# Sheet1.net
KiCad netlist of a schematic drawn in Altium Designer
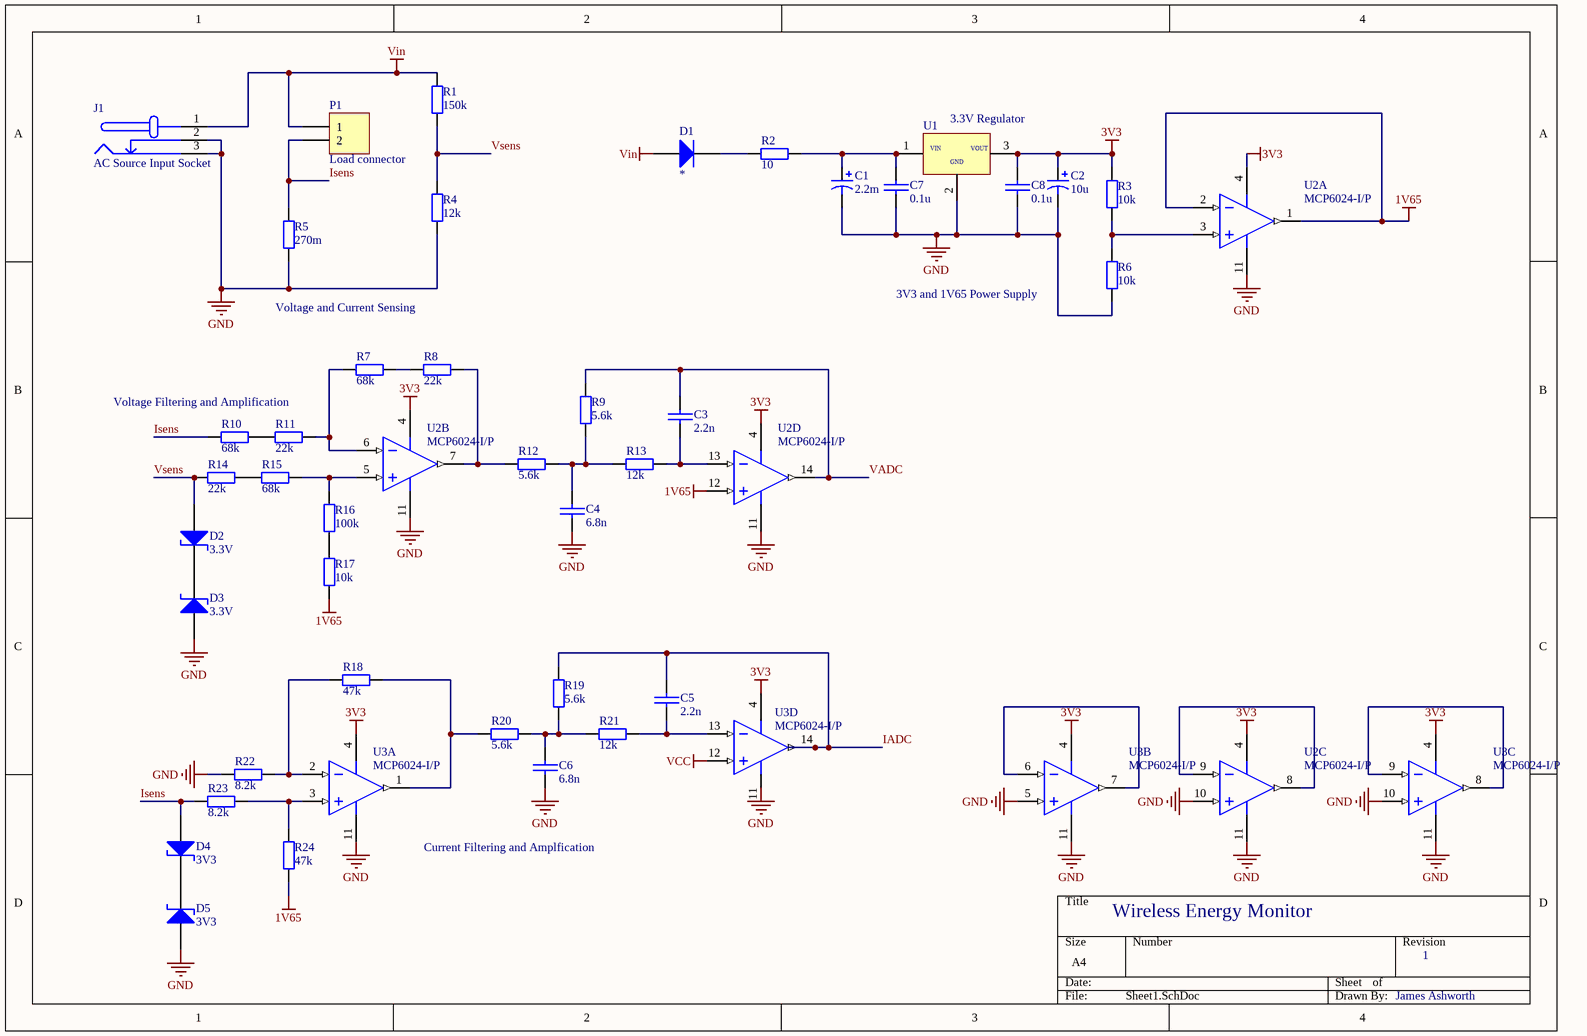
[diagram p0: Sheet1.SchDoc]

(export (version "E")
  (design (tool "Eeschema 10.0.6"))
  (components
    (comp (ref "C1")
      (value "2.2m")
      (footprint "CAP-RAD-7.5mm Pitch")
      (description "Polarized Capacitor (Axial)")
      (fields (field (name "PUBLISHER") "Altium Limited"))
      (libsource (lib "EE209_SCHLibrary") (part "Cap Pol (220uF-470uF)"))
    )
    (comp (ref "C2")
      (value "10u")
      (footprint "CAP-RAD-3mm Pitch")
      (description "Polarized Capacitor (Axial)")
      (fields (field (name "PUBLISHER") "Altium Limited"))
      (libsource (lib "EE209_SCHLibrary") (part "Cap Pol (22uF-100uF)"))
    )
    (comp (ref "C3")
      (value "2.2n")
      (footprint "ECE-CAPR0.2x0.1TH")
      (description "CAP CER 10pF 50V TH")
      (libsource (lib "EceParts") (part "Cap"))
    )
    (comp (ref "C4")
      (value "6.8n")
      (footprint "ECE-CAPR0.2x0.1TH")
      (description "CAP CER 10pF 50V TH")
      (libsource (lib "EceParts") (part "Cap"))
    )
    (comp (ref "C5")
      (value "2.2n")
      (footprint "ECE-CAPR0.2x0.1TH")
      (description "CAP CER 10pF 50V TH")
      (libsource (lib "EceParts") (part "Cap"))
    )
    (comp (ref "C6")
      (value "6.8n")
      (footprint "ECE-CAPR0.2x0.1TH")
      (description "CAP CER 10pF 50V TH")
      (libsource (lib "EceParts") (part "Cap"))
    )
    (comp (ref "C7")
      (value "0.1u")
      (footprint "ECE-CAPR0.2x0.1TH")
      (description "CAP CER 10pF 50V TH")
      (libsource (lib "EceParts") (part "Cap"))
    )
    (comp (ref "C8")
      (value "0.1u")
      (footprint "ECE-CAPR0.2x0.1TH")
      (description "CAP CER 10pF 50V TH")
      (libsource (lib "EceParts") (part "Cap"))
    )
    (comp (ref "D1")
      (value "*")
      (footprint "AXIAL-DIODE-0.4")
      (fields
        (field (name "MANUFACTURER") "Fairchild Semiconductor")
        (field (name "PUBLISHER") "Altium Limited")
      )
      (libsource (lib "EE209_SCHLibrary") (part "Diode"))
    )
    (comp (ref "D2")
      (value "3.3V")
      (footprint "AXIAL-DIODE-0.4")
      (description "Zener Diode")
      (libsource (lib "EE209_SCHLibrary") (part "Zener"))
    )
    (comp (ref "D3")
      (value "3.3V")
      (footprint "AXIAL-DIODE-0.4")
      (description "Zener Diode")
      (libsource (lib "EE209_SCHLibrary") (part "Zener"))
    )
    (comp (ref "D4")
      (value "3V3")
      (footprint "AXIAL-DIODE-0.4")
      (description "Zener Diode")
      (libsource (lib "EE209_SCHLibrary") (part "Zener"))
    )
    (comp (ref "D5")
      (value "3V3")
      (footprint "AXIAL-DIODE-0.4")
      (description "Zener Diode")
      (libsource (lib "EE209_SCHLibrary") (part "Zener"))
    )
    (comp (ref "J1")
      (value "AC Source Input Socket")
      (footprint "AC-Socket")
      (libsource (lib "EE209_SCHLibrary") (part "AC Input"))
    )
    (comp (ref "P1")
      (value "Load connector")
      (footprint "Dual Banana Plug")
      (description "M6 Holes")
      (fields (field (name "PUBLISHER") "Altium Limited"))
      (libsource (lib "EE209_SCHLibrary") (part "Dual Banana Plugs"))
    )
    (comp (ref "R1")
      (value "150k")
      (footprint "AXIAL-0.4")
      (description "Through Hole Resistor")
      (fields (field (name "PUBLISHER") "Altium Limited"))
      (libsource (lib "") (part "Res_1"))
    )
    (comp (ref "R2")
      (value "10")
      (footprint "AXIAL-0.4")
      (description "Through Hole Resistor")
      (fields (field (name "PUBLISHER") "Altium Limited"))
      (libsource (lib "EE209_SCHLibrary") (part "Res"))
    )
    (comp (ref "R3")
      (value "10k")
      (footprint "AXIAL-0.4")
      (description "Through Hole Resistor")
      (fields (field (name "PUBLISHER") "Altium Limited"))
      (libsource (lib "") (part "Res_1"))
    )
    (comp (ref "R4")
      (value "12k")
      (footprint "AXIAL-0.4")
      (description "Through Hole Resistor")
      (fields (field (name "PUBLISHER") "Altium Limited"))
      (libsource (lib "") (part "Res_1"))
    )
    (comp (ref "R5")
      (value "270m")
      (footprint "0805 RES")
      (description "Through Hole Resistor")
      (fields (field (name "PUBLISHER") "Altium Limited"))
      (libsource (lib "") (part "Res_1"))
    )
    (comp (ref "R6")
      (value "10k")
      (footprint "AXIAL-0.4")
      (description "Through Hole Resistor")
      (fields (field (name "PUBLISHER") "Altium Limited"))
      (libsource (lib "") (part "Res_1"))
    )
    (comp (ref "R7")
      (value "68k")
      (footprint "AXIAL-0.4")
      (description "Through Hole Resistor")
      (fields (field (name "PUBLISHER") "Altium Limited"))
      (libsource (lib "EE209_SCHLibrary") (part "Res"))
    )
    (comp (ref "R8")
      (value "22k")
      (footprint "AXIAL-0.4")
      (description "Through Hole Resistor")
      (fields (field (name "PUBLISHER") "Altium Limited"))
      (libsource (lib "EE209_SCHLibrary") (part "Res"))
    )
    (comp (ref "R9")
      (value "5.6k")
      (footprint "0805 RES")
      (description "Through Hole Resistor")
      (fields (field (name "PUBLISHER") "Altium Limited"))
      (libsource (lib "") (part "Res_1"))
    )
    (comp (ref "R10")
      (value "68k")
      (footprint "AXIAL-0.4")
      (description "Through Hole Resistor")
      (fields (field (name "PUBLISHER") "Altium Limited"))
      (libsource (lib "EE209_SCHLibrary") (part "Res"))
    )
    (comp (ref "R11")
      (value "22k")
      (footprint "AXIAL-0.4")
      (description "Through Hole Resistor")
      (fields (field (name "PUBLISHER") "Altium Limited"))
      (libsource (lib "EE209_SCHLibrary") (part "Res"))
    )
    (comp (ref "R12")
      (value "5.6k")
      (footprint "AXIAL-0.4")
      (description "Through Hole Resistor")
      (fields (field (name "PUBLISHER") "Altium Limited"))
      (libsource (lib "EE209_SCHLibrary") (part "Res"))
    )
    (comp (ref "R13")
      (value "12k")
      (footprint "0805 RES")
      (description "Through Hole Resistor")
      (fields (field (name "PUBLISHER") "Altium Limited"))
      (libsource (lib "") (part "Res_2"))
    )
    (comp (ref "R14")
      (value "22k")
      (footprint "AXIAL-0.4")
      (description "Through Hole Resistor")
      (fields (field (name "PUBLISHER") "Altium Limited"))
      (libsource (lib "EE209_SCHLibrary") (part "Res"))
    )
    (comp (ref "R15")
      (value "68k")
      (footprint "AXIAL-0.4")
      (description "Through Hole Resistor")
      (fields (field (name "PUBLISHER") "Altium Limited"))
      (libsource (lib "EE209_SCHLibrary") (part "Res"))
    )
    (comp (ref "R16")
      (value "100k")
      (footprint "AXIAL-0.4")
      (description "Through Hole Resistor")
      (fields (field (name "PUBLISHER") "Altium Limited"))
      (libsource (lib "") (part "Res_1"))
    )
    (comp (ref "R17")
      (value "10k")
      (footprint "AXIAL-0.4")
      (description "Through Hole Resistor")
      (fields (field (name "PUBLISHER") "Altium Limited"))
      (libsource (lib "") (part "Res_1"))
    )
    (comp (ref "R18")
      (value "47k")
      (footprint "AXIAL-0.4")
      (description "Through Hole Resistor")
      (fields (field (name "PUBLISHER") "Altium Limited"))
      (libsource (lib "") (part "Res_2"))
    )
    (comp (ref "R19")
      (value "5.6k")
      (footprint "AXIAL-0.4")
      (description "Through Hole Resistor")
      (fields (field (name "PUBLISHER") "Altium Limited"))
      (libsource (lib "") (part "Res_3"))
    )
    (comp (ref "R20")
      (value "5.6k")
      (footprint "AXIAL-0.4")
      (description "Through Hole Resistor")
      (fields (field (name "PUBLISHER") "Altium Limited"))
      (libsource (lib "") (part "Res_2"))
    )
    (comp (ref "R21")
      (value "12k")
      (footprint "AXIAL-0.4")
      (description "Through Hole Resistor")
      (fields (field (name "PUBLISHER") "Altium Limited"))
      (libsource (lib "") (part "Res_2"))
    )
    (comp (ref "R22")
      (value "8.2k")
      (footprint "AXIAL-0.4")
      (description "Through Hole Resistor")
      (fields (field (name "PUBLISHER") "Altium Limited"))
      (libsource (lib "EE209_SCHLibrary") (part "Res"))
    )
    (comp (ref "R23")
      (value "8.2k")
      (footprint "AXIAL-0.4")
      (description "Through Hole Resistor")
      (fields (field (name "PUBLISHER") "Altium Limited"))
      (libsource (lib "EE209_SCHLibrary") (part "Res"))
    )
    (comp (ref "R24")
      (value "47k")
      (footprint "AXIAL-0.4")
      (description "Through Hole Resistor")
      (fields (field (name "PUBLISHER") "Altium Limited"))
      (libsource (lib "") (part "Res_1"))
    )
    (comp (ref "U1")
      (value "3.3V Regulator")
      (footprint "TO-92")
      (libsource (lib "EE209_SCHLibrary") (part "LP2950-33"))
    )
    (comp (ref "U2")
      (value "MCP6024-I/P")
      (footprint "DIP-14")
      (description "Rail-to-Rail Input/Output, 10 MHz Operational Amplifier, 14-Pin PDIP, Industrial Temperature")
      (fields (field (name "PUBLISHER") "Altium Limited"))
      (libsource (lib "EE209_SCHLibrary") (part "MCP6024-I/P"))
    )
    (comp (ref "U3")
      (value "MCP6024-I/P")
      (footprint "DIP-14")
      (description "Rail-to-Rail Input/Output, 10 MHz Operational Amplifier, 14-Pin PDIP, Industrial Temperature")
      (fields (field (name "PUBLISHER") "Altium Limited"))
      (libsource (lib "EE209_SCHLibrary") (part "MCP6024-I/P"))
    )
  )
  (nets
    (net (code "1") (name "/IADC") (class "Default")
      (node (ref "C5") (pin "1") (pinfunction "1_1") (pintype "passive"))
      (node (ref "R19") (pin "1") (pinfunction "1_1") (pintype "passive"))
      (node (ref "U3") (pin "14") (pinfunction "VOUTD_14") (pintype "output"))
    )
    (net (code "2") (name "/Isens") (class "Default")
      (node (ref "D4") (pin "1") (pinfunction "A_1") (pintype "passive"))
      (node (ref "P1") (pin "2") (pinfunction "2_2") (pintype "passive"))
      (node (ref "R10") (pin "1") (pinfunction "1_1") (pintype "passive"))
      (node (ref "R23") (pin "1") (pinfunction "1_1") (pintype "passive"))
      (node (ref "R5") (pin "2") (pinfunction "2_2") (pintype "passive"))
    )
    (net (code "3") (name "/VADC") (class "Default")
      (node (ref "C3") (pin "1") (pinfunction "1_1") (pintype "passive"))
      (node (ref "R9") (pin "2") (pinfunction "2_2") (pintype "passive"))
      (node (ref "U2") (pin "14") (pinfunction "VOUTD_14") (pintype "output"))
    )
    (net (code "4") (name "/Vsens") (class "Default")
      (node (ref "D2") (pin "1") (pinfunction "A_1") (pintype "passive"))
      (node (ref "R1") (pin "1") (pinfunction "1_1") (pintype "passive"))
      (node (ref "R14") (pin "1") (pinfunction "1_1") (pintype "passive"))
      (node (ref "R4") (pin "2") (pinfunction "2_2") (pintype "passive"))
    )
    (net (code "5") (name "1V65") (class "Default")
      (node (ref "R17") (pin "1") (pinfunction "1_1") (pintype "passive"))
      (node (ref "R24") (pin "1") (pinfunction "1_1") (pintype "passive"))
      (node (ref "U2") (pin "1") (pinfunction "VOUTA_1") (pintype "output"))
      (node (ref "U2") (pin "12") (pinfunction "VIND+_12") (pintype "input"))
      (node (ref "U2") (pin "2") (pinfunction "VINA-_2") (pintype "input"))
    )
    (net (code "6") (name "3V3") (class "Default")
      (node (ref "C2") (pin "1") (pinfunction "1_1") (pintype "passive"))
      (node (ref "C8") (pin "1") (pinfunction "1_1") (pintype "passive"))
      (node (ref "R3") (pin "2") (pinfunction "2_2") (pintype "passive"))
      (node (ref "U1") (pin "3") (pinfunction "OUTPUT_3") (pintype "passive"))
      (node (ref "U2") (pin "4") (pinfunction "VDD_4") (pintype "power_in"))
      (node (ref "U3") (pin "4") (pinfunction "VDD_4") (pintype "power_in"))
    )
    (net (code "7") (name "GND") (class "Default")
      (node (ref "C1") (pin "2") (pinfunction "2_2") (pintype "passive"))
      (node (ref "C2") (pin "2") (pinfunction "2_2") (pintype "passive"))
      (node (ref "C4") (pin "2") (pinfunction "2_2") (pintype "passive"))
      (node (ref "C6") (pin "2") (pinfunction "2_2") (pintype "passive"))
      (node (ref "C7") (pin "2") (pinfunction "2_2") (pintype "passive"))
      (node (ref "C8") (pin "2") (pinfunction "2_2") (pintype "passive"))
      (node (ref "D3") (pin "1") (pinfunction "A_1") (pintype "passive"))
      (node (ref "D5") (pin "1") (pinfunction "A_1") (pintype "passive"))
      (node (ref "J1") (pin "2") (pinfunction "GND_ALT_2") (pintype "power_in"))
      (node (ref "J1") (pin "3") (pinfunction "GND_3") (pintype "power_in"))
      (node (ref "R22") (pin "1") (pinfunction "1_1") (pintype "passive"))
      (node (ref "R4") (pin "1") (pinfunction "1_1") (pintype "passive"))
      (node (ref "R5") (pin "1") (pinfunction "1_1") (pintype "passive"))
      (node (ref "R6") (pin "1") (pinfunction "1_1") (pintype "passive"))
      (node (ref "U1") (pin "2") (pinfunction "GND_2") (pintype "passive"))
      (node (ref "U2") (pin "10") (pinfunction "VINC+_10") (pintype "input"))
      (node (ref "U2") (pin "11") (pinfunction "VSS_11") (pintype "power_in"))
      (node (ref "U3") (pin "10") (pinfunction "VINC+_10") (pintype "input"))
      (node (ref "U3") (pin "11") (pinfunction "VSS_11") (pintype "power_in"))
      (node (ref "U3") (pin "5") (pinfunction "VINB+_5") (pintype "input"))
    )
    (net (code "8") (name "Net-(C4-Pad1)") (class "Default")
      (node (ref "C4") (pin "1") (pinfunction "1_1") (pintype "passive"))
      (node (ref "R12") (pin "2") (pinfunction "2_2") (pintype "passive"))
      (node (ref "R13") (pin "2") (pinfunction "2_2") (pintype "passive"))
      (node (ref "R9") (pin "1") (pinfunction "1_1") (pintype "passive"))
    )
    (net (code "9") (name "Net-(C6-Pad1)") (class "Default")
      (node (ref "C6") (pin "1") (pinfunction "1_1") (pintype "passive"))
      (node (ref "R19") (pin "2") (pinfunction "2_2") (pintype "passive"))
      (node (ref "R20") (pin "1") (pinfunction "1_1") (pintype "passive"))
      (node (ref "R21") (pin "2") (pinfunction "2_2") (pintype "passive"))
    )
    (net (code "10") (name "Net-(D1-K)") (class "Default")
      (node (ref "D1") (pin "2") (pinfunction "K_2") (pintype "passive"))
      (node (ref "R2") (pin "1") (pinfunction "1_1") (pintype "passive"))
    )
    (net (code "11") (name "Net-(D2-K)") (class "Default")
      (node (ref "D2") (pin "2") (pinfunction "K_2") (pintype "passive"))
      (node (ref "D3") (pin "2") (pinfunction "K_2") (pintype "passive"))
    )
    (net (code "12") (name "Net-(D4-K)") (class "Default")
      (node (ref "D4") (pin "2") (pinfunction "K_2") (pintype "passive"))
      (node (ref "D5") (pin "2") (pinfunction "K_2") (pintype "passive"))
    )
    (net (code "13") (name "Net-(R7-Pad2)") (class "Default")
      (node (ref "R7") (pin "2") (pinfunction "2_2") (pintype "passive"))
      (node (ref "R8") (pin "1") (pinfunction "1_1") (pintype "passive"))
    )
    (net (code "14") (name "Net-(R10-Pad2)") (class "Default")
      (node (ref "R10") (pin "2") (pinfunction "2_2") (pintype "passive"))
      (node (ref "R11") (pin "1") (pinfunction "1_1") (pintype "passive"))
    )
    (net (code "15") (name "Net-(R14-Pad2)") (class "Default")
      (node (ref "R14") (pin "2") (pinfunction "2_2") (pintype "passive"))
      (node (ref "R15") (pin "1") (pinfunction "1_1") (pintype "passive"))
    )
    (net (code "16") (name "Net-(R16-Pad1)") (class "Default")
      (node (ref "R16") (pin "1") (pinfunction "1_1") (pintype "passive"))
      (node (ref "R17") (pin "2") (pinfunction "2_2") (pintype "passive"))
    )
    (net (code "17") (name "Net-(U1-INPUT)") (class "Default")
      (node (ref "C1") (pin "1") (pinfunction "1_1") (pintype "passive"))
      (node (ref "C7") (pin "1") (pinfunction "1_1") (pintype "passive"))
      (node (ref "R2") (pin "2") (pinfunction "2_2") (pintype "passive"))
      (node (ref "U1") (pin "1") (pinfunction "INPUT_1") (pintype "passive"))
    )
    (net (code "18") (name "Net-(U2A-VINA+)") (class "Default")
      (node (ref "R3") (pin "1") (pinfunction "1_1") (pintype "passive"))
      (node (ref "R6") (pin "2") (pinfunction "2_2") (pintype "passive"))
      (node (ref "U2") (pin "3") (pinfunction "VINA+_3") (pintype "input"))
    )
    (net (code "19") (name "Net-(U2B-VINB+)") (class "Default")
      (node (ref "R15") (pin "2") (pinfunction "2_2") (pintype "passive"))
      (node (ref "R16") (pin "2") (pinfunction "2_2") (pintype "passive"))
      (node (ref "U2") (pin "5") (pinfunction "VINB+_5") (pintype "input"))
    )
    (net (code "20") (name "Net-(U2B-VINB-)") (class "Default")
      (node (ref "R11") (pin "2") (pinfunction "2_2") (pintype "passive"))
      (node (ref "R7") (pin "1") (pinfunction "1_1") (pintype "passive"))
      (node (ref "U2") (pin "6") (pinfunction "VINB-_6") (pintype "input"))
    )
    (net (code "21") (name "Net-(U2B-VOUTB)") (class "Default")
      (node (ref "R12") (pin "1") (pinfunction "1_1") (pintype "passive"))
      (node (ref "R8") (pin "2") (pinfunction "2_2") (pintype "passive"))
      (node (ref "U2") (pin "7") (pinfunction "VOUTB_7") (pintype "output"))
    )
    (net (code "22") (name "Net-(U2C-VINC-)") (class "Default")
      (node (ref "U2") (pin "8") (pinfunction "VOUTC_8") (pintype "output"))
      (node (ref "U2") (pin "9") (pinfunction "VINC-_9") (pintype "input"))
    )
    (net (code "23") (name "Net-(U2D-VIND-)") (class "Default")
      (node (ref "C3") (pin "2") (pinfunction "2_2") (pintype "passive"))
      (node (ref "R13") (pin "1") (pinfunction "1_1") (pintype "passive"))
      (node (ref "U2") (pin "13") (pinfunction "VIND-_13") (pintype "input"))
    )
    (net (code "24") (name "Net-(U3A-VINA+)") (class "Default")
      (node (ref "R23") (pin "2") (pinfunction "2_2") (pintype "passive"))
      (node (ref "R24") (pin "2") (pinfunction "2_2") (pintype "passive"))
      (node (ref "U3") (pin "3") (pinfunction "VINA+_3") (pintype "input"))
    )
    (net (code "25") (name "Net-(U3A-VINA-)") (class "Default")
      (node (ref "R18") (pin "2") (pinfunction "2_2") (pintype "passive"))
      (node (ref "R22") (pin "2") (pinfunction "2_2") (pintype "passive"))
      (node (ref "U3") (pin "2") (pinfunction "VINA-_2") (pintype "input"))
    )
    (net (code "26") (name "Net-(U3A-VOUTA)") (class "Default")
      (node (ref "R18") (pin "1") (pinfunction "1_1") (pintype "passive"))
      (node (ref "R20") (pin "2") (pinfunction "2_2") (pintype "passive"))
      (node (ref "U3") (pin "1") (pinfunction "VOUTA_1") (pintype "output"))
    )
    (net (code "27") (name "Net-(U3B-VINB-)") (class "Default")
      (node (ref "U3") (pin "6") (pinfunction "VINB-_6") (pintype "input"))
      (node (ref "U3") (pin "7") (pinfunction "VOUTB_7") (pintype "output"))
    )
    (net (code "28") (name "Net-(U3C-VINC-)") (class "Default")
      (node (ref "U3") (pin "8") (pinfunction "VOUTC_8") (pintype "output"))
      (node (ref "U3") (pin "9") (pinfunction "VINC-_9") (pintype "input"))
    )
    (net (code "29") (name "Net-(U3D-VIND-)") (class "Default")
      (node (ref "C5") (pin "2") (pinfunction "2_2") (pintype "passive"))
      (node (ref "R21") (pin "1") (pinfunction "1_1") (pintype "passive"))
      (node (ref "U3") (pin "13") (pinfunction "VIND-_13") (pintype "input"))
    )
    (net (code "30") (name "VCC") (class "Default")
      (node (ref "U3") (pin "12") (pinfunction "VIND+_12") (pintype "input"))
    )
    (net (code "31") (name "Vin") (class "Default")
      (node (ref "D1") (pin "1") (pinfunction "A_1") (pintype "passive"))
      (node (ref "J1") (pin "1") (pinfunction "VCC_1") (pintype "power_in"))
      (node (ref "P1") (pin "1") (pinfunction "1_1") (pintype "passive"))
      (node (ref "R1") (pin "2") (pinfunction "2_2") (pintype "passive"))
    )
    (net (code "32") (name "unconnected-(U3D-VSS-Pad11)") (class "Default")
      (node (ref "U3") (pin "11") (pinfunction "VSS_11") (pintype "power_in"))
    )
  )
)
